# OVP_OIP_12V.net
KiCad netlist of a schematic drawn in Altium Designer
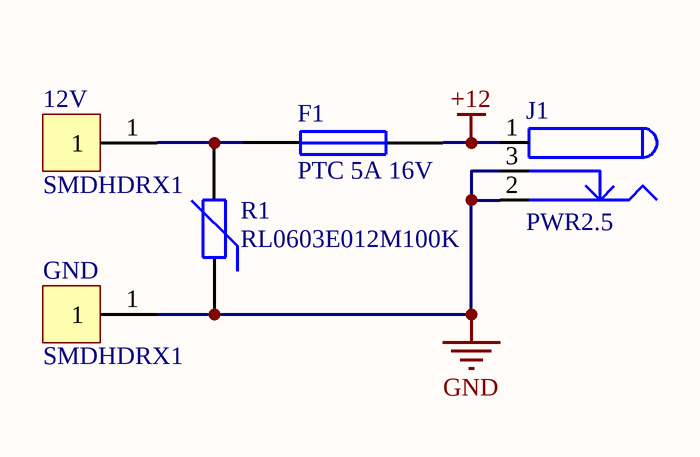
[diagram p0: OVP_OIP_12V.SchDoc]

(export (version "E")
  (design (tool "Eeschema 10.0.6"))
  (components
    (comp (ref "12V")
      (value "SMDHDRX1")
      (footprint "SMDHDRX1_6*4")
      (description "SMA and Hole")
      (libsource (lib "Schlib_Cbp") (part "SMDHDRX1"))
    )
    (comp (ref "F1")
      (value "PTC 5A 16V")
      (footprint "2920")
      (description "Fuse")
      (fields (field (name "PUBLISHER") "Altium Limited"))
      (libsource (lib "Miscellaneous Devices") (part "Fuse 1"))
    )
    (comp (ref "GND")
      (value "SMDHDRX1")
      (footprint "SMDHDRX1_6*4")
      (description "SMA and Hole")
      (libsource (lib "Schlib_Cbp") (part "SMDHDRX1"))
    )
    (comp (ref "J1") (value "PWR2.5") (footprint "DC005F") (libsource (lib "ADLib_CBP") (part "PWR2.5")))
    (comp (ref "R1")
      (value "RL0603E012M100K")
      (footprint "0603_R")
      (description "Varistor (Voltage-Sensitive Resistor)")
      (fields (field (name "PUBLISHER") "Altium Limited"))
      (libsource (lib "Miscellaneous Devices") (part "Res Varistor"))
    )
  )
  (nets
    (net (code "1") (name "+12") (class "Default")
      (node (ref "F1") (pin "2") (pinfunction "2_2") (pintype "passive"))
      (node (ref "J1") (pin "1") (pinfunction "1_1") (pintype "passive"))
    )
    (net (code "2") (name "GND") (class "Default")
      (node (ref "GND") (pin "1") (pinfunction "1_1") (pintype "passive"))
      (node (ref "J1") (pin "2") (pinfunction "2_2") (pintype "passive"))
      (node (ref "J1") (pin "3") (pinfunction "3_3") (pintype "passive"))
      (node (ref "R1") (pin "1") (pinfunction "1_1") (pintype "passive"))
    )
    (net (code "3") (name "Net-(12V-Pad1)") (class "Default")
      (node (ref "12V") (pin "1") (pinfunction "1_1") (pintype "passive"))
      (node (ref "F1") (pin "1") (pinfunction "1_1") (pintype "passive"))
      (node (ref "R1") (pin "2") (pinfunction "2_2") (pintype "passive"))
    )
  )
)
